# harmonicAnalyzer.net
KiCad netlist of a schematic drawn in Altium Designer
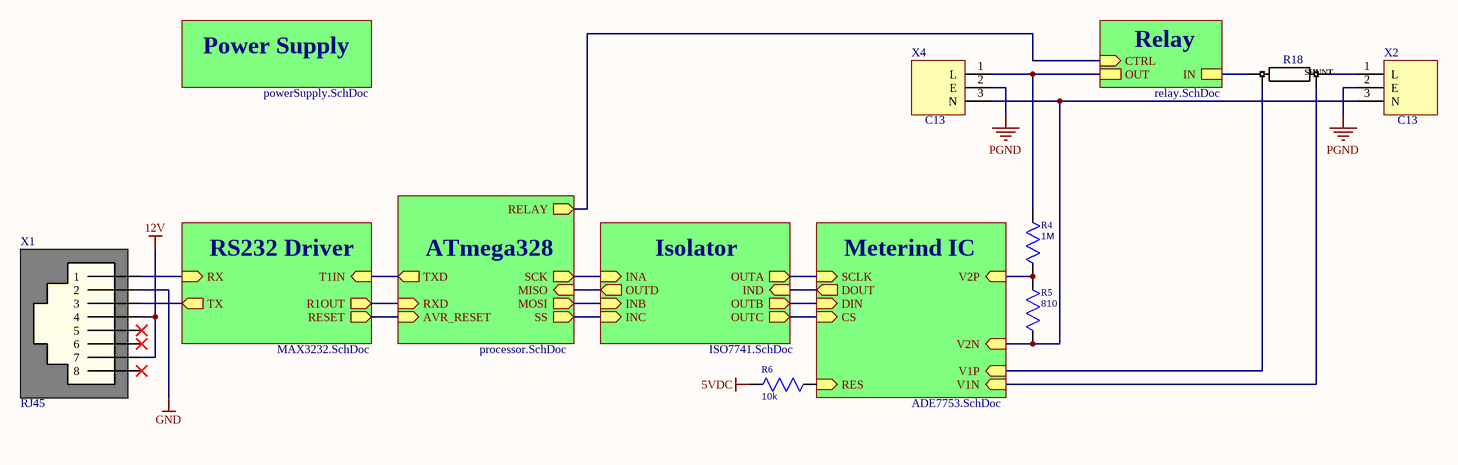
[diagram p0: harmonicAnalyzer.SchDoc]

(export (version "E")
  (design (tool "Eeschema 10.0.6"))
  (components
    (comp (ref "R4")
      (value "1M")
      (footprint "R_0805")
      (description "Resistor")
      (libsource (lib "AX_Altium_v2.3") (part "R0805"))
    )
    (comp (ref "R5")
      (value "810")
      (footprint "R_0805")
      (description "Resistor")
      (libsource (lib "AX_Altium_v2.3") (part "R0805"))
    )
    (comp (ref "R6")
      (value "10k")
      (footprint "R_0603")
      (description "Resistor")
      (libsource (lib "AX_Altium_v2.3") (part "R0603"))
    )
    (comp (ref "R18")
      (value "SHUNT")
      (footprint "WSHP2818")
      (description "Current Shunt")
      (libsource (lib "SmartOutletIntegratedLibrary") (part "SHUNT"))
    )
    (comp (ref "X1")
      (value "RJ45")
      (footprint "RJ45")
      (description "Outlet YH-55-05 8P8C 5521")
      (libsource (lib "SmartOutletIntegratedLibrary") (part "RJ45"))
    )
    (comp (ref "X2")
      (value "C13")
      (footprint "C13_RA_TH")
      (libsource (lib "SmartOutletIntegratedLibrary") (part "C13"))
    )
    (comp (ref "X4") (value "C13") (footprint "C13_RA_TH") (libsource (lib "") (part "C13_1")))
  )
  (nets
    (net (code "2") (name "/IN") (class "Default")
      (node (ref "R18") (pin "2") (pinfunction "2_2") (pintype "passive"))
    )
    (net (code "4") (name "/OUT") (class "Default")
      (node (ref "R4") (pin "1") (pintype "passive"))
      (node (ref "X4") (pin "1") (pinfunction "L_1") (pintype "passive"))
    )
    (net (code "11") (name "/RES") (class "Default") (node (ref "R6") (pin "2") (pintype "passive")))
    (net (code "13") (name "/RX") (class "Default")
      (node (ref "X1") (pin "1") (pinfunction "1_1") (pintype "passive"))
    )
    (net (code "16") (name "/TX") (class "Default")
      (node (ref "X1") (pin "3") (pinfunction "3_3") (pintype "passive"))
    )
    (net (code "18") (name "/V1N") (class "Default")
      (node (ref "R18") (pin "3") (pinfunction "3_3") (pintype "passive"))
    )
    (net (code "19") (name "/V1P") (class "Default")
      (node (ref "R18") (pin "4") (pinfunction "4_4") (pintype "passive"))
    )
    (net (code "20") (name "/V2N") (class "Default")
      (node (ref "R5") (pin "2") (pintype "passive"))
      (node (ref "X2") (pin "3") (pinfunction "N_3") (pintype "passive"))
      (node (ref "X4") (pin "3") (pinfunction "N_3") (pintype "passive"))
    )
    (net (code "21") (name "/V2P") (class "Default")
      (node (ref "R4") (pin "2") (pintype "passive"))
      (node (ref "R5") (pin "1") (pintype "passive"))
    )
    (net (code "22") (name "5VDC") (class "Default") (node (ref "R6") (pin "1") (pintype "passive")))
    (net (code "23") (name "12V") (class "Default")
      (node (ref "X1") (pin "4") (pinfunction "4_4") (pintype "passive"))
      (node (ref "X1") (pin "7") (pinfunction "7_7") (pintype "passive"))
    )
    (net (code "24") (name "GND") (class "Default")
      (node (ref "X1") (pin "2") (pinfunction "2_2") (pintype "passive"))
    )
    (net (code "25") (name "Net-(X2-L)") (class "Default")
      (node (ref "R18") (pin "1") (pinfunction "1_1") (pintype "passive"))
      (node (ref "X2") (pin "1") (pinfunction "L_1") (pintype "passive"))
    )
    (net (code "26") (name "PGND") (class "Default")
      (node (ref "X2") (pin "2") (pinfunction "E_2") (pintype "passive"))
      (node (ref "X4") (pin "2") (pinfunction "E_2") (pintype "passive"))
    )
    (net (code "27") (name "unconnected-(X1-Pad5)") (class "Default")
      (node (ref "X1") (pin "5") (pinfunction "5_5") (pintype "passive+no_connect"))
    )
    (net (code "28") (name "unconnected-(X1-Pad6)") (class "Default")
      (node (ref "X1") (pin "6") (pinfunction "6_6") (pintype "passive+no_connect"))
    )
    (net (code "29") (name "unconnected-(X1-Pad8)") (class "Default")
      (node (ref "X1") (pin "8") (pinfunction "8_8") (pintype "passive+no_connect"))
    )
  )
)
